# MotorControl.net
KiCad netlist of a schematic drawn in Altium Designer
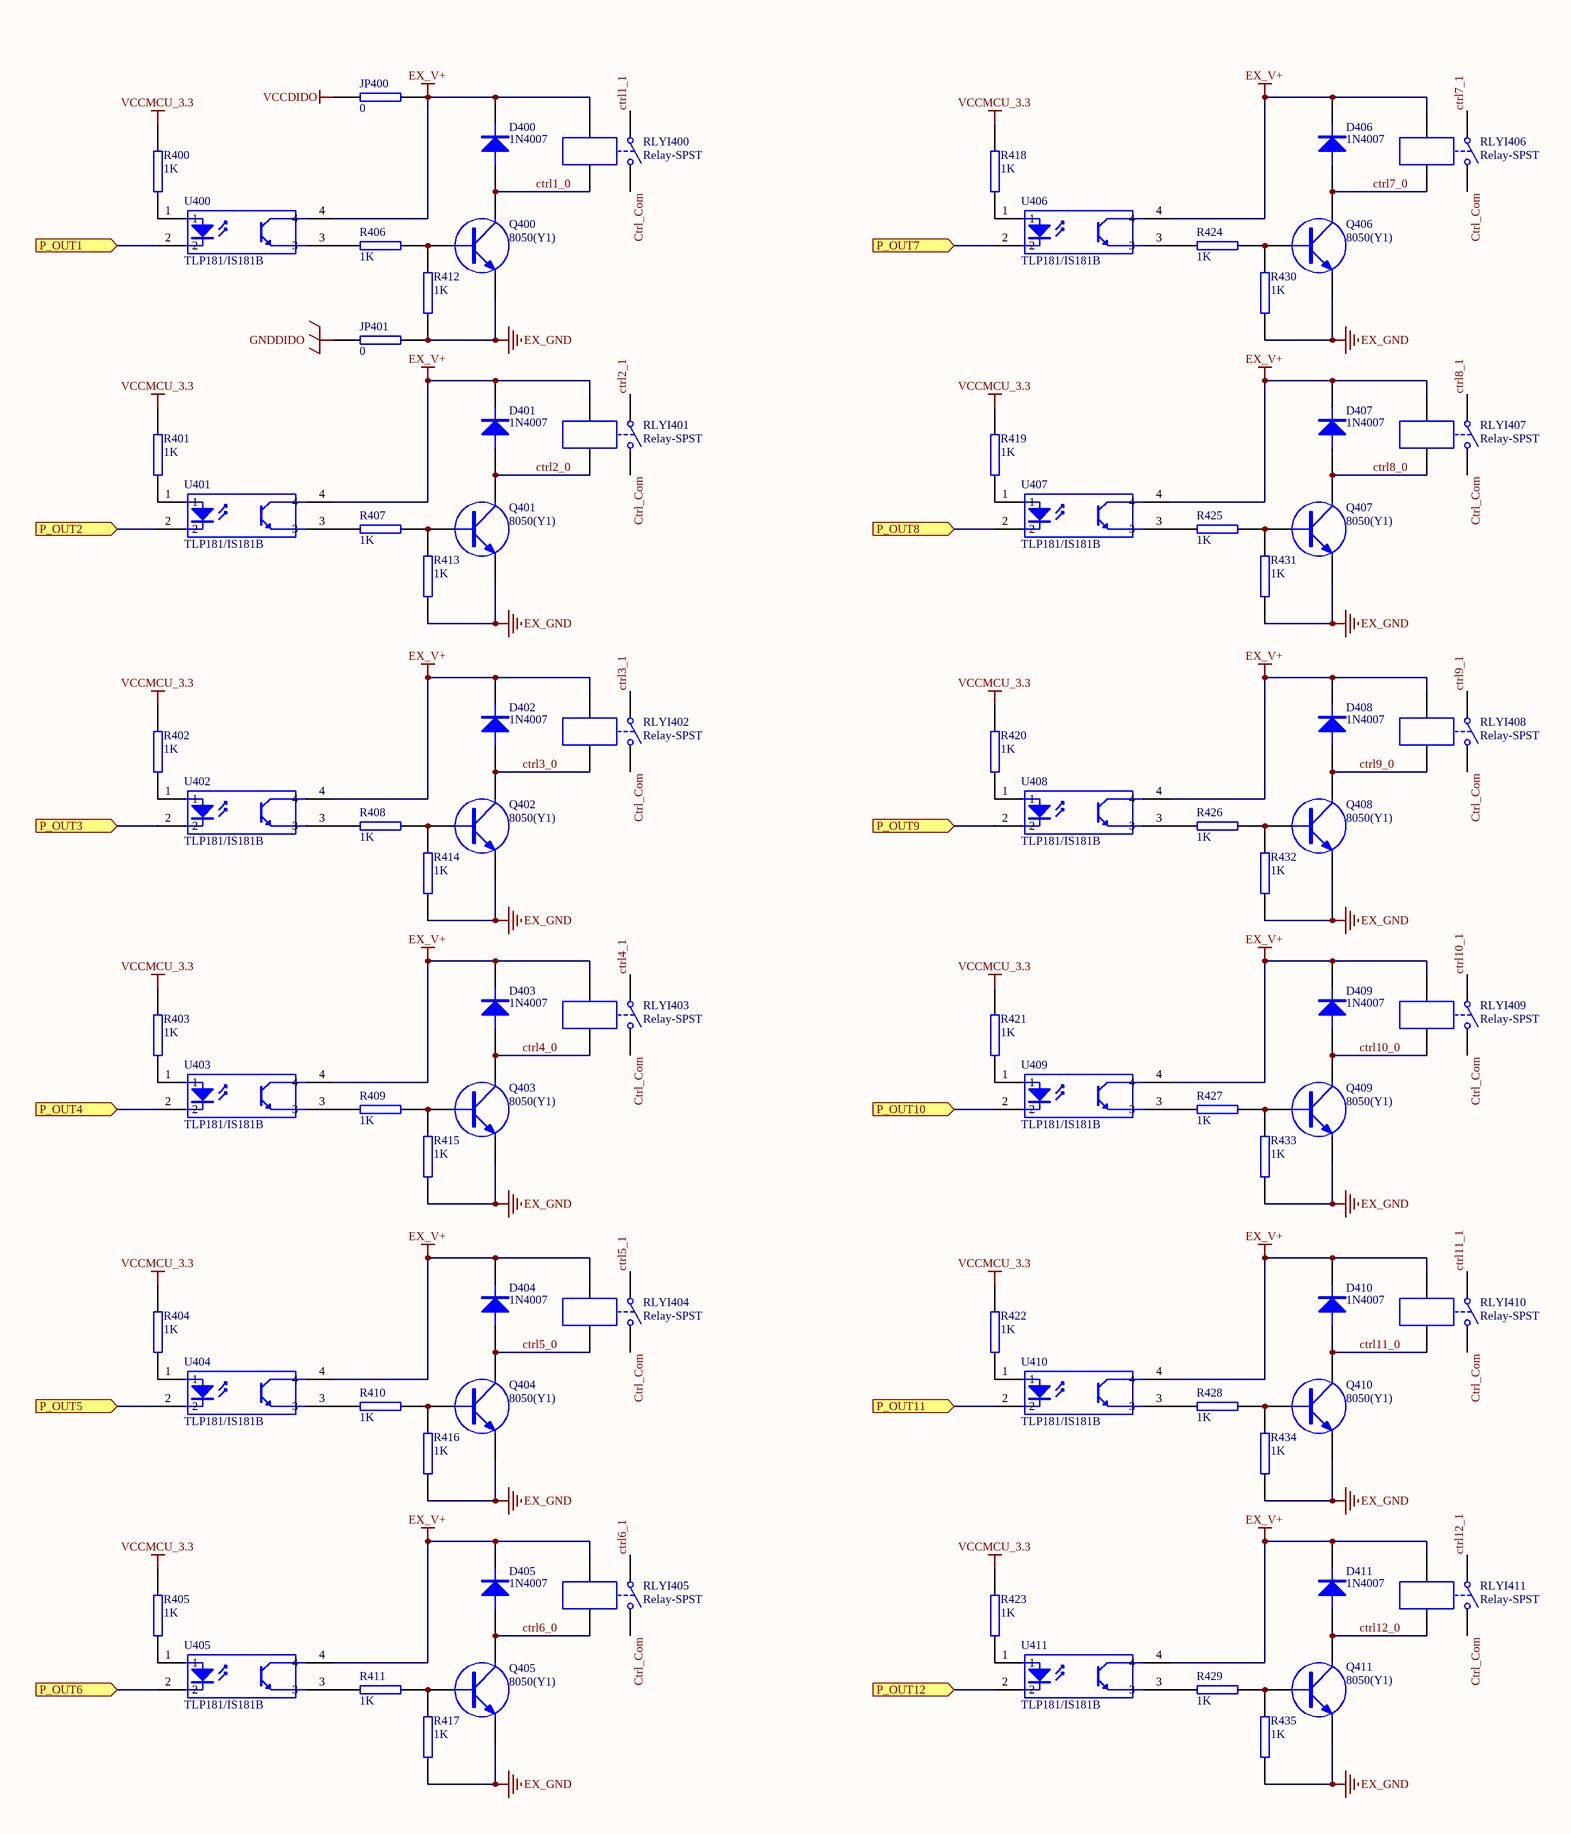
[diagram p0: MotorControl.SchDoc, left]
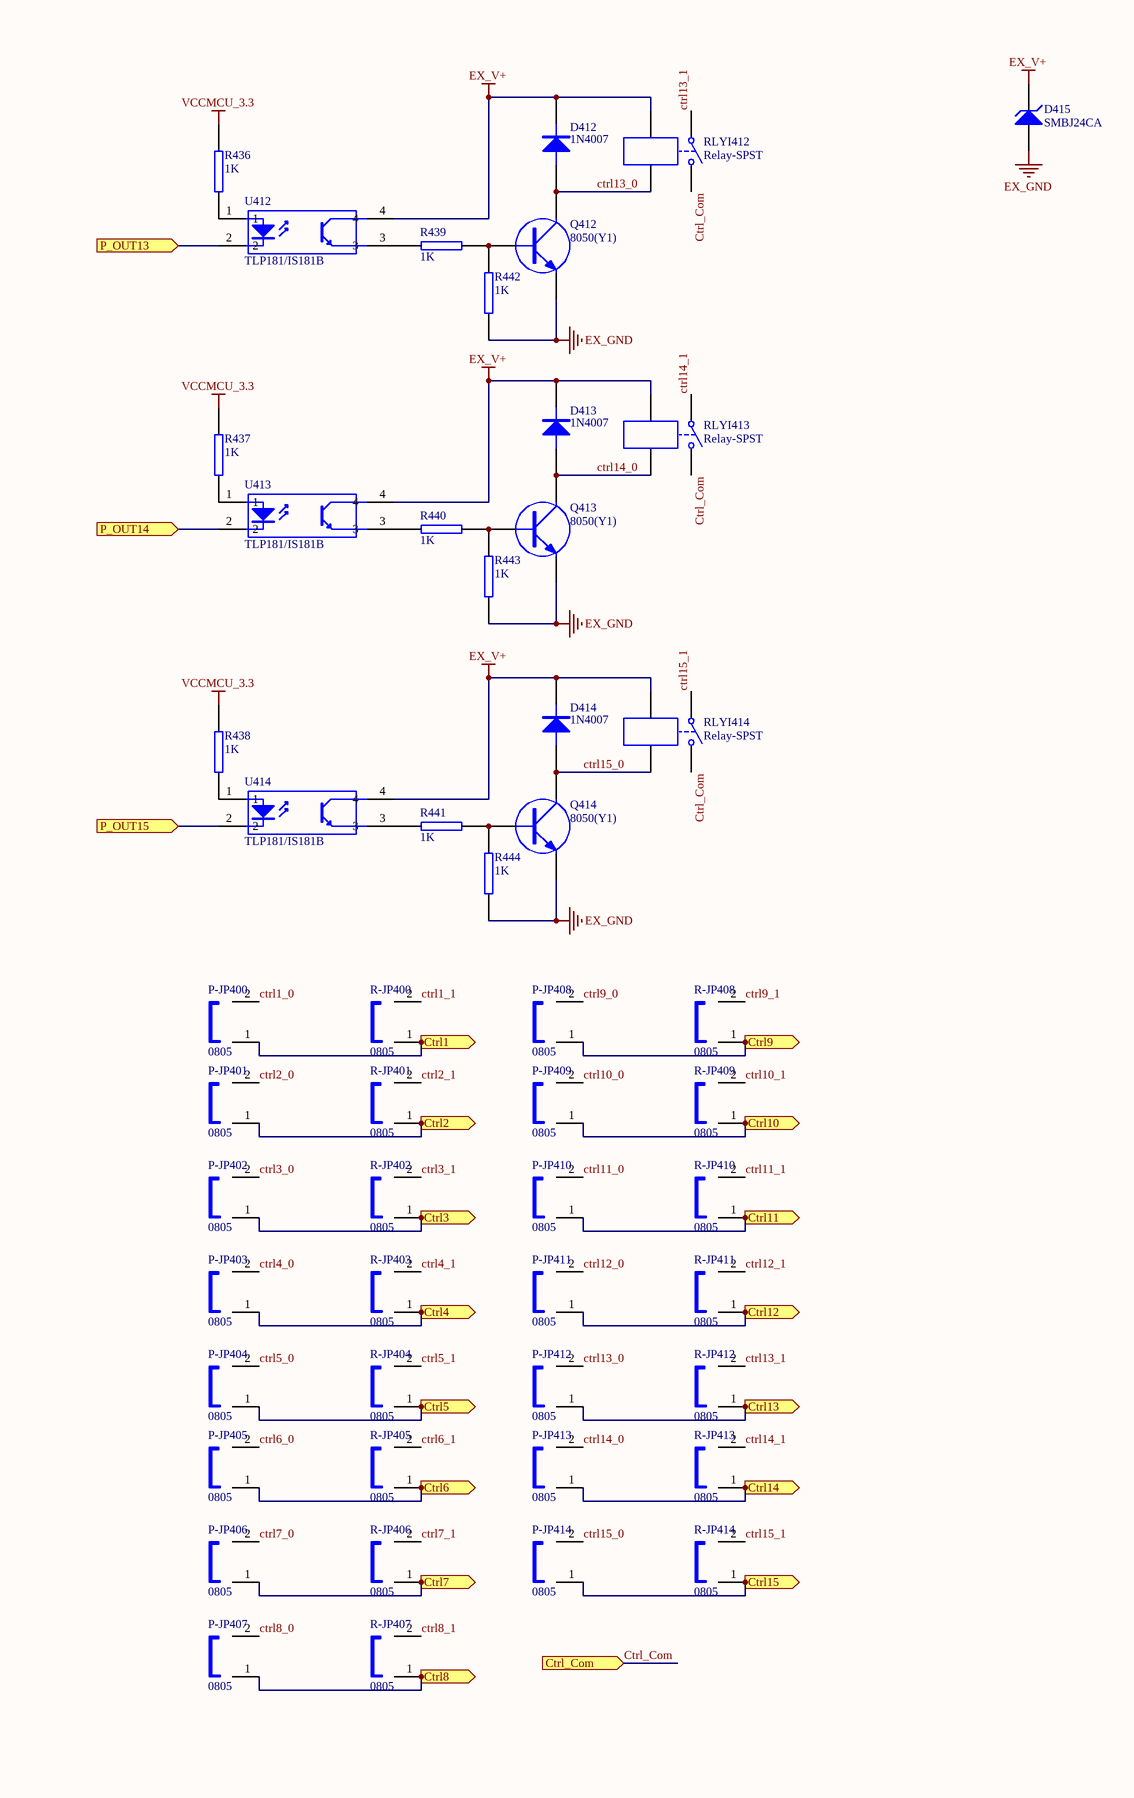
[diagram p1: MotorControl.SchDoc, right]

(export (version "E")
  (design (tool "Eeschema 10.0.6"))
  (components
    (comp (ref "D400")
      (value "1N4007")
      (footprint "SMA")
      (description "Diode")
      (libsource (lib "*") (part "DIODE"))
    )
    (comp (ref "D401")
      (value "1N4007")
      (footprint "SMA")
      (description "Diode")
      (libsource (lib "*") (part "DIODE"))
    )
    (comp (ref "D402")
      (value "1N4007")
      (footprint "SMA")
      (description "Diode")
      (libsource (lib "*") (part "DIODE"))
    )
    (comp (ref "D403")
      (value "1N4007")
      (footprint "SMA")
      (description "Diode")
      (libsource (lib "*") (part "DIODE"))
    )
    (comp (ref "D404")
      (value "1N4007")
      (footprint "SMA")
      (description "Diode")
      (libsource (lib "*") (part "DIODE"))
    )
    (comp (ref "D405")
      (value "1N4007")
      (footprint "SMA")
      (description "Diode")
      (libsource (lib "*") (part "DIODE"))
    )
    (comp (ref "D406")
      (value "1N4007")
      (footprint "SMA")
      (description "Diode")
      (libsource (lib "*") (part "DIODE"))
    )
    (comp (ref "D407")
      (value "1N4007")
      (footprint "SMA")
      (description "Diode")
      (libsource (lib "*") (part "DIODE"))
    )
    (comp (ref "D408")
      (value "1N4007")
      (footprint "SMA")
      (description "Diode")
      (libsource (lib "*") (part "DIODE"))
    )
    (comp (ref "D409")
      (value "1N4007")
      (footprint "SMA")
      (description "Diode")
      (libsource (lib "*") (part "DIODE"))
    )
    (comp (ref "D410")
      (value "1N4007")
      (footprint "SMA")
      (description "Diode")
      (libsource (lib "*") (part "DIODE"))
    )
    (comp (ref "D411")
      (value "1N4007")
      (footprint "SMA")
      (description "Diode")
      (libsource (lib "*") (part "DIODE"))
    )
    (comp (ref "D412")
      (value "1N4007")
      (footprint "SMA")
      (description "Diode")
      (libsource (lib "*") (part "DIODE"))
    )
    (comp (ref "D413")
      (value "1N4007")
      (footprint "SMA")
      (description "Diode")
      (libsource (lib "*") (part "DIODE"))
    )
    (comp (ref "D414")
      (value "1N4007")
      (footprint "SMA")
      (description "Diode")
      (libsource (lib "*") (part "DIODE"))
    )
    (comp (ref "D415")
      (value "SMBJ24CA")
      (footprint "SMB")
      (description "Zener Diode")
      (fields (field (name "PUBLISHER") "Altium Limited"))
      (libsource (lib "YGInfoSCHLib") (part "D Zener"))
    )
    (comp (ref "JP400") (value "0") (footprint "RESC_E0805_2012X50N") (libsource (lib "*") (part "RES2")))
    (comp (ref "JP401") (value "0") (footprint "RESC_E0805_2012X50N") (libsource (lib "*") (part "RES2")))
    (comp (ref "P-JP400")
      (value "0805")
      (footprint "RESC_E0805_2012X50N")
      (description "Jumper")
      (libsource (lib "YGInfoSCHLib") (part "JUMPER"))
    )
    (comp (ref "P-JP401")
      (value "0805")
      (footprint "RESC_E0805_2012X50N")
      (description "Jumper")
      (libsource (lib "YGInfoSCHLib") (part "JUMPER"))
    )
    (comp (ref "P-JP402")
      (value "0805")
      (footprint "RESC_E0805_2012X50N")
      (description "Jumper")
      (libsource (lib "YGInfoSCHLib") (part "JUMPER"))
    )
    (comp (ref "P-JP403")
      (value "0805")
      (footprint "RESC_E0805_2012X50N")
      (description "Jumper")
      (libsource (lib "YGInfoSCHLib") (part "JUMPER"))
    )
    (comp (ref "P-JP404")
      (value "0805")
      (footprint "RESC_E0805_2012X50N")
      (description "Jumper")
      (libsource (lib "YGInfoSCHLib") (part "JUMPER"))
    )
    (comp (ref "P-JP405")
      (value "0805")
      (footprint "RESC_E0805_2012X50N")
      (description "Jumper")
      (libsource (lib "YGInfoSCHLib") (part "JUMPER"))
    )
    (comp (ref "P-JP406")
      (value "0805")
      (footprint "RESC_E0805_2012X50N")
      (description "Jumper")
      (libsource (lib "YGInfoSCHLib") (part "JUMPER"))
    )
    (comp (ref "P-JP407")
      (value "0805")
      (footprint "RESC_E0805_2012X50N")
      (description "Jumper")
      (libsource (lib "YGInfoSCHLib") (part "JUMPER"))
    )
    (comp (ref "P-JP408")
      (value "0805")
      (footprint "RESC_E0805_2012X50N")
      (description "Jumper")
      (libsource (lib "YGInfoSCHLib") (part "JUMPER"))
    )
    (comp (ref "P-JP409")
      (value "0805")
      (footprint "RESC_E0805_2012X50N")
      (description "Jumper")
      (libsource (lib "YGInfoSCHLib") (part "JUMPER"))
    )
    (comp (ref "P-JP410")
      (value "0805")
      (footprint "RESC_E0805_2012X50N")
      (description "Jumper")
      (libsource (lib "YGInfoSCHLib") (part "JUMPER"))
    )
    (comp (ref "P-JP411")
      (value "0805")
      (footprint "RESC_E0805_2012X50N")
      (description "Jumper")
      (libsource (lib "YGInfoSCHLib") (part "JUMPER"))
    )
    (comp (ref "P-JP412")
      (value "0805")
      (footprint "RESC_E0805_2012X50N")
      (description "Jumper")
      (libsource (lib "YGInfoSCHLib") (part "JUMPER"))
    )
    (comp (ref "P-JP413")
      (value "0805")
      (footprint "RESC_E0805_2012X50N")
      (description "Jumper")
      (libsource (lib "YGInfoSCHLib") (part "JUMPER"))
    )
    (comp (ref "P-JP414")
      (value "0805")
      (footprint "RESC_E0805_2012X50N")
      (description "Jumper")
      (libsource (lib "YGInfoSCHLib") (part "JUMPER"))
    )
    (comp (ref "Q400")
      (value "8050(Y1)")
      (footprint "SOT23_95P280X110-3N")
      (libsource (lib "*") (part "BSS64"))
    )
    (comp (ref "Q401")
      (value "8050(Y1)")
      (footprint "SOT23_95P280X110-3N")
      (libsource (lib "*") (part "BSS64"))
    )
    (comp (ref "Q402")
      (value "8050(Y1)")
      (footprint "SOT23_95P280X110-3N")
      (libsource (lib "*") (part "BSS64"))
    )
    (comp (ref "Q403")
      (value "8050(Y1)")
      (footprint "SOT23_95P280X110-3N")
      (libsource (lib "*") (part "BSS64"))
    )
    (comp (ref "Q404")
      (value "8050(Y1)")
      (footprint "SOT23_95P280X110-3N")
      (libsource (lib "*") (part "BSS64"))
    )
    (comp (ref "Q405")
      (value "8050(Y1)")
      (footprint "SOT23_95P280X110-3N")
      (libsource (lib "*") (part "BSS64"))
    )
    (comp (ref "Q406")
      (value "8050(Y1)")
      (footprint "SOT23_95P280X110-3N")
      (libsource (lib "*") (part "BSS64"))
    )
    (comp (ref "Q407")
      (value "8050(Y1)")
      (footprint "SOT23_95P280X110-3N")
      (libsource (lib "*") (part "BSS64"))
    )
    (comp (ref "Q408")
      (value "8050(Y1)")
      (footprint "SOT23_95P280X110-3N")
      (libsource (lib "*") (part "BSS64"))
    )
    (comp (ref "Q409")
      (value "8050(Y1)")
      (footprint "SOT23_95P280X110-3N")
      (libsource (lib "*") (part "BSS64"))
    )
    (comp (ref "Q410")
      (value "8050(Y1)")
      (footprint "SOT23_95P280X110-3N")
      (libsource (lib "*") (part "BSS64"))
    )
    (comp (ref "Q411")
      (value "8050(Y1)")
      (footprint "SOT23_95P280X110-3N")
      (libsource (lib "*") (part "BSS64"))
    )
    (comp (ref "Q412")
      (value "8050(Y1)")
      (footprint "SOT23_95P280X110-3N")
      (libsource (lib "*") (part "BSS64"))
    )
    (comp (ref "Q413")
      (value "8050(Y1)")
      (footprint "SOT23_95P280X110-3N")
      (libsource (lib "*") (part "BSS64"))
    )
    (comp (ref "Q414")
      (value "8050(Y1)")
      (footprint "SOT23_95P280X110-3N")
      (libsource (lib "*") (part "BSS64"))
    )
    (comp (ref "R-JP400")
      (value "0805")
      (footprint "RESC_E0805_2012X50N")
      (description "Jumper")
      (libsource (lib "YGInfoSCHLib") (part "JUMPER"))
    )
    (comp (ref "R-JP401")
      (value "0805")
      (footprint "RESC_E0805_2012X50N")
      (description "Jumper")
      (libsource (lib "YGInfoSCHLib") (part "JUMPER"))
    )
    (comp (ref "R-JP402")
      (value "0805")
      (footprint "RESC_E0805_2012X50N")
      (description "Jumper")
      (libsource (lib "YGInfoSCHLib") (part "JUMPER"))
    )
    (comp (ref "R-JP403")
      (value "0805")
      (footprint "RESC_E0805_2012X50N")
      (description "Jumper")
      (libsource (lib "YGInfoSCHLib") (part "JUMPER"))
    )
    (comp (ref "R-JP404")
      (value "0805")
      (footprint "RESC_E0805_2012X50N")
      (description "Jumper")
      (libsource (lib "YGInfoSCHLib") (part "JUMPER"))
    )
    (comp (ref "R-JP405")
      (value "0805")
      (footprint "RESC_E0805_2012X50N")
      (description "Jumper")
      (libsource (lib "YGInfoSCHLib") (part "JUMPER"))
    )
    (comp (ref "R-JP406")
      (value "0805")
      (footprint "RESC_E0805_2012X50N")
      (description "Jumper")
      (libsource (lib "YGInfoSCHLib") (part "JUMPER"))
    )
    (comp (ref "R-JP407")
      (value "0805")
      (footprint "RESC_E0805_2012X50N")
      (description "Jumper")
      (libsource (lib "YGInfoSCHLib") (part "JUMPER"))
    )
    (comp (ref "R-JP408")
      (value "0805")
      (footprint "RESC_E0805_2012X50N")
      (description "Jumper")
      (libsource (lib "YGInfoSCHLib") (part "JUMPER"))
    )
    (comp (ref "R-JP409")
      (value "0805")
      (footprint "RESC_E0805_2012X50N")
      (description "Jumper")
      (libsource (lib "YGInfoSCHLib") (part "JUMPER"))
    )
    (comp (ref "R-JP410")
      (value "0805")
      (footprint "RESC_E0805_2012X50N")
      (description "Jumper")
      (libsource (lib "YGInfoSCHLib") (part "JUMPER"))
    )
    (comp (ref "R-JP411")
      (value "0805")
      (footprint "RESC_E0805_2012X50N")
      (description "Jumper")
      (libsource (lib "YGInfoSCHLib") (part "JUMPER"))
    )
    (comp (ref "R-JP412")
      (value "0805")
      (footprint "RESC_E0805_2012X50N")
      (description "Jumper")
      (libsource (lib "YGInfoSCHLib") (part "JUMPER"))
    )
    (comp (ref "R-JP413")
      (value "0805")
      (footprint "RESC_E0805_2012X50N")
      (description "Jumper")
      (libsource (lib "YGInfoSCHLib") (part "JUMPER"))
    )
    (comp (ref "R-JP414")
      (value "0805")
      (footprint "RESC_E0805_2012X50N")
      (description "Jumper")
      (libsource (lib "YGInfoSCHLib") (part "JUMPER"))
    )
    (comp (ref "R400") (value "1K") (footprint "RESC_E0805_2012X50N") (libsource (lib "*") (part "RES2")))
    (comp (ref "R401") (value "1K") (footprint "RESC_E0805_2012X50N") (libsource (lib "*") (part "RES2")))
    (comp (ref "R402") (value "1K") (footprint "RESC_E0805_2012X50N") (libsource (lib "*") (part "RES2")))
    (comp (ref "R403") (value "1K") (footprint "RESC_E0805_2012X50N") (libsource (lib "*") (part "RES2")))
    (comp (ref "R404") (value "1K") (footprint "RESC_E0805_2012X50N") (libsource (lib "*") (part "RES2")))
    (comp (ref "R405") (value "1K") (footprint "RESC_E0805_2012X50N") (libsource (lib "*") (part "RES2")))
    (comp (ref "R406") (value "1K") (footprint "RESC_E0805_2012X50N") (libsource (lib "*") (part "RES2")))
    (comp (ref "R407") (value "1K") (footprint "RESC_E0805_2012X50N") (libsource (lib "*") (part "RES2")))
    (comp (ref "R408") (value "1K") (footprint "RESC_E0805_2012X50N") (libsource (lib "*") (part "RES2")))
    (comp (ref "R409") (value "1K") (footprint "RESC_E0805_2012X50N") (libsource (lib "*") (part "RES2")))
    (comp (ref "R410") (value "1K") (footprint "RESC_E0805_2012X50N") (libsource (lib "*") (part "RES2")))
    (comp (ref "R411") (value "1K") (footprint "RESC_E0805_2012X50N") (libsource (lib "*") (part "RES2")))
    (comp (ref "R412") (value "1K") (footprint "RESC_E0805_2012X50N") (libsource (lib "*") (part "RES2")))
    (comp (ref "R413") (value "1K") (footprint "RESC_E0805_2012X50N") (libsource (lib "*") (part "RES2")))
    (comp (ref "R414") (value "1K") (footprint "RESC_E0805_2012X50N") (libsource (lib "*") (part "RES2")))
    (comp (ref "R415") (value "1K") (footprint "RESC_E0805_2012X50N") (libsource (lib "*") (part "RES2")))
    (comp (ref "R416") (value "1K") (footprint "RESC_E0805_2012X50N") (libsource (lib "*") (part "RES2")))
    (comp (ref "R417") (value "1K") (footprint "RESC_E0805_2012X50N") (libsource (lib "*") (part "RES2")))
    (comp (ref "R418") (value "1K") (footprint "RESC_E0805_2012X50N") (libsource (lib "*") (part "RES2")))
    (comp (ref "R419") (value "1K") (footprint "RESC_E0805_2012X50N") (libsource (lib "*") (part "RES2")))
    (comp (ref "R420") (value "1K") (footprint "RESC_E0805_2012X50N") (libsource (lib "*") (part "RES2")))
    (comp (ref "R421") (value "1K") (footprint "RESC_E0805_2012X50N") (libsource (lib "*") (part "RES2")))
    (comp (ref "R422") (value "1K") (footprint "RESC_E0805_2012X50N") (libsource (lib "*") (part "RES2")))
    (comp (ref "R423") (value "1K") (footprint "RESC_E0805_2012X50N") (libsource (lib "*") (part "RES2")))
    (comp (ref "R424") (value "1K") (footprint "RESC_E0805_2012X50N") (libsource (lib "*") (part "RES2")))
    (comp (ref "R425") (value "1K") (footprint "RESC_E0805_2012X50N") (libsource (lib "*") (part "RES2")))
    (comp (ref "R426") (value "1K") (footprint "RESC_E0805_2012X50N") (libsource (lib "*") (part "RES2")))
    (comp (ref "R427") (value "1K") (footprint "RESC_E0805_2012X50N") (libsource (lib "*") (part "RES2")))
    (comp (ref "R428") (value "1K") (footprint "RESC_E0805_2012X50N") (libsource (lib "*") (part "RES2")))
    (comp (ref "R429") (value "1K") (footprint "RESC_E0805_2012X50N") (libsource (lib "*") (part "RES2")))
    (comp (ref "R430") (value "1K") (footprint "RESC_E0805_2012X50N") (libsource (lib "*") (part "RES2")))
    (comp (ref "R431") (value "1K") (footprint "RESC_E0805_2012X50N") (libsource (lib "*") (part "RES2")))
    (comp (ref "R432") (value "1K") (footprint "RESC_E0805_2012X50N") (libsource (lib "*") (part "RES2")))
    (comp (ref "R433") (value "1K") (footprint "RESC_E0805_2012X50N") (libsource (lib "*") (part "RES2")))
    (comp (ref "R434") (value "1K") (footprint "RESC_E0805_2012X50N") (libsource (lib "*") (part "RES2")))
    (comp (ref "R435") (value "1K") (footprint "RESC_E0805_2012X50N") (libsource (lib "*") (part "RES2")))
    (comp (ref "R436") (value "1K") (footprint "RESC_E0805_2012X50N") (libsource (lib "*") (part "RES2")))
    (comp (ref "R437") (value "1K") (footprint "RESC_E0805_2012X50N") (libsource (lib "*") (part "RES2")))
    (comp (ref "R438") (value "1K") (footprint "RESC_E0805_2012X50N") (libsource (lib "*") (part "RES2")))
    (comp (ref "R439") (value "1K") (footprint "RESC_E0805_2012X50N") (libsource (lib "*") (part "RES2")))
    (comp (ref "R440") (value "1K") (footprint "RESC_E0805_2012X50N") (libsource (lib "*") (part "RES2")))
    (comp (ref "R441") (value "1K") (footprint "RESC_E0805_2012X50N") (libsource (lib "*") (part "RES2")))
    (comp (ref "R442") (value "1K") (footprint "RESC_E0805_2012X50N") (libsource (lib "*") (part "RES2")))
    (comp (ref "R443") (value "1K") (footprint "RESC_E0805_2012X50N") (libsource (lib "*") (part "RES2")))
    (comp (ref "R444") (value "1K") (footprint "RESC_E0805_2012X50N") (libsource (lib "*") (part "RES2")))
    (comp (ref "RLYI400")
      (value "Relay-SPST")
      (footprint "JDQ24V")
      (description "Single-Pole Single-Throw Relay")
      (fields (field (name "PUBLISHER") "Altium Limited"))
      (libsource (lib "Miscellaneous Devices") (part "Relay-SPST"))
    )
    (comp (ref "RLYI401")
      (value "Relay-SPST")
      (footprint "JDQ24V")
      (description "Single-Pole Single-Throw Relay")
      (fields (field (name "PUBLISHER") "Altium Limited"))
      (libsource (lib "Miscellaneous Devices") (part "Relay-SPST"))
    )
    (comp (ref "RLYI402")
      (value "Relay-SPST")
      (footprint "JDQ24V")
      (description "Single-Pole Single-Throw Relay")
      (fields (field (name "PUBLISHER") "Altium Limited"))
      (libsource (lib "Miscellaneous Devices") (part "Relay-SPST"))
    )
    (comp (ref "RLYI403")
      (value "Relay-SPST")
      (footprint "JDQ24V")
      (description "Single-Pole Single-Throw Relay")
      (fields (field (name "PUBLISHER") "Altium Limited"))
      (libsource (lib "Miscellaneous Devices") (part "Relay-SPST"))
    )
    (comp (ref "RLYI404")
      (value "Relay-SPST")
      (footprint "JDQ24V")
      (description "Single-Pole Single-Throw Relay")
      (fields (field (name "PUBLISHER") "Altium Limited"))
      (libsource (lib "Miscellaneous Devices") (part "Relay-SPST"))
    )
    (comp (ref "RLYI405")
      (value "Relay-SPST")
      (footprint "JDQ24V")
      (description "Single-Pole Single-Throw Relay")
      (fields (field (name "PUBLISHER") "Altium Limited"))
      (libsource (lib "Miscellaneous Devices") (part "Relay-SPST"))
    )
    (comp (ref "RLYI406")
      (value "Relay-SPST")
      (footprint "JDQ24V")
      (description "Single-Pole Single-Throw Relay")
      (fields (field (name "PUBLISHER") "Altium Limited"))
      (libsource (lib "Miscellaneous Devices") (part "Relay-SPST"))
    )
    (comp (ref "RLYI407")
      (value "Relay-SPST")
      (footprint "JDQ24V")
      (description "Single-Pole Single-Throw Relay")
      (fields (field (name "PUBLISHER") "Altium Limited"))
      (libsource (lib "Miscellaneous Devices") (part "Relay-SPST"))
    )
    (comp (ref "RLYI408")
      (value "Relay-SPST")
      (footprint "JDQ24V")
      (description "Single-Pole Single-Throw Relay")
      (fields (field (name "PUBLISHER") "Altium Limited"))
      (libsource (lib "Miscellaneous Devices") (part "Relay-SPST"))
    )
    (comp (ref "RLYI409")
      (value "Relay-SPST")
      (footprint "JDQ24V")
      (description "Single-Pole Single-Throw Relay")
      (fields (field (name "PUBLISHER") "Altium Limited"))
      (libsource (lib "Miscellaneous Devices") (part "Relay-SPST"))
    )
    (comp (ref "RLYI410")
      (value "Relay-SPST")
      (footprint "JDQ24V")
      (description "Single-Pole Single-Throw Relay")
      (fields (field (name "PUBLISHER") "Altium Limited"))
      (libsource (lib "Miscellaneous Devices") (part "Relay-SPST"))
    )
    (comp (ref "RLYI411")
      (value "Relay-SPST")
      (footprint "JDQ24V")
      (description "Single-Pole Single-Throw Relay")
      (fields (field (name "PUBLISHER") "Altium Limited"))
      (libsource (lib "Miscellaneous Devices") (part "Relay-SPST"))
    )
    (comp (ref "RLYI412")
      (value "Relay-SPST")
      (footprint "JDQ24V")
      (description "Single-Pole Single-Throw Relay")
      (fields (field (name "PUBLISHER") "Altium Limited"))
      (libsource (lib "Miscellaneous Devices") (part "Relay-SPST"))
    )
    (comp (ref "RLYI413")
      (value "Relay-SPST")
      (footprint "JDQ24V")
      (description "Single-Pole Single-Throw Relay")
      (fields (field (name "PUBLISHER") "Altium Limited"))
      (libsource (lib "Miscellaneous Devices") (part "Relay-SPST"))
    )
    (comp (ref "RLYI414")
      (value "Relay-SPST")
      (footprint "JDQ24V")
      (description "Single-Pole Single-Throw Relay")
      (fields (field (name "PUBLISHER") "Altium Limited"))
      (libsource (lib "Miscellaneous Devices") (part "Relay-SPST"))
    )
    (comp (ref "U400")
      (value "TLP181/IS181B")
      (footprint "TLP181")
      (description "光耦隔离")
      (libsource (lib "YGInfoSCHLib") (part "TLP181"))
    )
    (comp (ref "U401")
      (value "TLP181/IS181B")
      (footprint "TLP181")
      (description "光耦隔离")
      (libsource (lib "YGInfoSCHLib") (part "TLP181"))
    )
    (comp (ref "U402")
      (value "TLP181/IS181B")
      (footprint "TLP181")
      (description "光耦隔离")
      (libsource (lib "YGInfoSCHLib") (part "TLP181"))
    )
    (comp (ref "U403")
      (value "TLP181/IS181B")
      (footprint "TLP181")
      (description "光耦隔离")
      (libsource (lib "YGInfoSCHLib") (part "TLP181"))
    )
    (comp (ref "U404")
      (value "TLP181/IS181B")
      (footprint "TLP181")
      (description "光耦隔离")
      (libsource (lib "YGInfoSCHLib") (part "TLP181"))
    )
    (comp (ref "U405")
      (value "TLP181/IS181B")
      (footprint "TLP181")
      (description "光耦隔离")
      (libsource (lib "YGInfoSCHLib") (part "TLP181"))
    )
    (comp (ref "U406")
      (value "TLP181/IS181B")
      (footprint "TLP181")
      (description "光耦隔离")
      (libsource (lib "YGInfoSCHLib") (part "TLP181"))
    )
    (comp (ref "U407")
      (value "TLP181/IS181B")
      (footprint "TLP181")
      (description "光耦隔离")
      (libsource (lib "YGInfoSCHLib") (part "TLP181"))
    )
    (comp (ref "U408")
      (value "TLP181/IS181B")
      (footprint "TLP181")
      (description "光耦隔离")
      (libsource (lib "YGInfoSCHLib") (part "TLP181"))
    )
    (comp (ref "U409")
      (value "TLP181/IS181B")
      (footprint "TLP181")
      (description "光耦隔离")
      (libsource (lib "YGInfoSCHLib") (part "TLP181"))
    )
    (comp (ref "U410")
      (value "TLP181/IS181B")
      (footprint "TLP181")
      (description "光耦隔离")
      (libsource (lib "YGInfoSCHLib") (part "TLP181"))
    )
    (comp (ref "U411")
      (value "TLP181/IS181B")
      (footprint "TLP181")
      (description "光耦隔离")
      (libsource (lib "YGInfoSCHLib") (part "TLP181"))
    )
    (comp (ref "U412")
      (value "TLP181/IS181B")
      (footprint "TLP181")
      (description "光耦隔离")
      (libsource (lib "YGInfoSCHLib") (part "TLP181"))
    )
    (comp (ref "U413")
      (value "TLP181/IS181B")
      (footprint "TLP181")
      (description "光耦隔离")
      (libsource (lib "YGInfoSCHLib") (part "TLP181"))
    )
    (comp (ref "U414")
      (value "TLP181/IS181B")
      (footprint "TLP181")
      (description "光耦隔离")
      (libsource (lib "YGInfoSCHLib") (part "TLP181"))
    )
  )
  (nets
    (net (code "1") (name "/Ctrl1") (class "Default")
      (node (ref "P-JP400") (pin "1") (pinfunction "1_1") (pintype "passive"))
      (node (ref "R-JP400") (pin "1") (pinfunction "1_1") (pintype "passive"))
    )
    (net (code "2") (name "/Ctrl2") (class "Default")
      (node (ref "P-JP401") (pin "1") (pinfunction "1_1") (pintype "passive"))
      (node (ref "R-JP401") (pin "1") (pinfunction "1_1") (pintype "passive"))
    )
    (net (code "3") (name "/Ctrl3") (class "Default")
      (node (ref "P-JP402") (pin "1") (pinfunction "1_1") (pintype "passive"))
      (node (ref "R-JP402") (pin "1") (pinfunction "1_1") (pintype "passive"))
    )
    (net (code "4") (name "/Ctrl4") (class "Default")
      (node (ref "P-JP403") (pin "1") (pinfunction "1_1") (pintype "passive"))
      (node (ref "R-JP403") (pin "1") (pinfunction "1_1") (pintype "passive"))
    )
    (net (code "5") (name "/Ctrl5") (class "Default")
      (node (ref "P-JP404") (pin "1") (pinfunction "1_1") (pintype "passive"))
      (node (ref "R-JP404") (pin "1") (pinfunction "1_1") (pintype "passive"))
    )
    (net (code "6") (name "/Ctrl6") (class "Default")
      (node (ref "P-JP405") (pin "1") (pinfunction "1_1") (pintype "passive"))
      (node (ref "R-JP405") (pin "1") (pinfunction "1_1") (pintype "passive"))
    )
    (net (code "7") (name "/Ctrl7") (class "Default")
      (node (ref "P-JP406") (pin "1") (pinfunction "1_1") (pintype "passive"))
      (node (ref "R-JP406") (pin "1") (pinfunction "1_1") (pintype "passive"))
    )
    (net (code "8") (name "/Ctrl8") (class "Default")
      (node (ref "P-JP407") (pin "1") (pinfunction "1_1") (pintype "passive"))
      (node (ref "R-JP407") (pin "1") (pinfunction "1_1") (pintype "passive"))
    )
    (net (code "9") (name "/Ctrl9") (class "Default")
      (node (ref "P-JP408") (pin "1") (pinfunction "1_1") (pintype "passive"))
      (node (ref "R-JP408") (pin "1") (pinfunction "1_1") (pintype "passive"))
    )
    (net (code "10") (name "/Ctrl10") (class "Default")
      (node (ref "P-JP409") (pin "1") (pinfunction "1_1") (pintype "passive"))
      (node (ref "R-JP409") (pin "1") (pinfunction "1_1") (pintype "passive"))
    )
    (net (code "11") (name "/Ctrl11") (class "Default")
      (node (ref "P-JP410") (pin "1") (pinfunction "1_1") (pintype "passive"))
      (node (ref "R-JP410") (pin "1") (pinfunction "1_1") (pintype "passive"))
    )
    (net (code "12") (name "/Ctrl12") (class "Default")
      (node (ref "P-JP411") (pin "1") (pinfunction "1_1") (pintype "passive"))
      (node (ref "R-JP411") (pin "1") (pinfunction "1_1") (pintype "passive"))
    )
    (net (code "13") (name "/Ctrl13") (class "Default")
      (node (ref "P-JP412") (pin "1") (pinfunction "1_1") (pintype "passive"))
      (node (ref "R-JP412") (pin "1") (pinfunction "1_1") (pintype "passive"))
    )
    (net (code "14") (name "/Ctrl14") (class "Default")
      (node (ref "P-JP413") (pin "1") (pinfunction "1_1") (pintype "passive"))
      (node (ref "R-JP413") (pin "1") (pinfunction "1_1") (pintype "passive"))
    )
    (net (code "15") (name "/Ctrl15") (class "Default")
      (node (ref "P-JP414") (pin "1") (pinfunction "1_1") (pintype "passive"))
      (node (ref "R-JP414") (pin "1") (pinfunction "1_1") (pintype "passive"))
    )
    (net (code "16") (name "/Ctrl_Com") (class "Default")
      (node (ref "RLYI400") (pin "2") (pinfunction "2_2") (pintype "passive"))
      (node (ref "RLYI401") (pin "2") (pinfunction "2_2") (pintype "passive"))
      (node (ref "RLYI402") (pin "2") (pinfunction "2_2") (pintype "passive"))
      (node (ref "RLYI403") (pin "2") (pinfunction "2_2") (pintype "passive"))
      (node (ref "RLYI404") (pin "2") (pinfunction "2_2") (pintype "passive"))
      (node (ref "RLYI405") (pin "2") (pinfunction "2_2") (pintype "passive"))
      (node (ref "RLYI406") (pin "2") (pinfunction "2_2") (pintype "passive"))
      (node (ref "RLYI407") (pin "2") (pinfunction "2_2") (pintype "passive"))
      (node (ref "RLYI408") (pin "2") (pinfunction "2_2") (pintype "passive"))
      (node (ref "RLYI409") (pin "2") (pinfunction "2_2") (pintype "passive"))
      (node (ref "RLYI410") (pin "2") (pinfunction "2_2") (pintype "passive"))
      (node (ref "RLYI411") (pin "2") (pinfunction "2_2") (pintype "passive"))
      (node (ref "RLYI412") (pin "2") (pinfunction "2_2") (pintype "passive"))
      (node (ref "RLYI413") (pin "2") (pinfunction "2_2") (pintype "passive"))
      (node (ref "RLYI414") (pin "2") (pinfunction "2_2") (pintype "passive"))
    )
    (net (code "17") (name "/P_OUT1") (class "Default")
      (node (ref "U400") (pin "2") (pinfunction "2_2") (pintype "passive"))
    )
    (net (code "18") (name "/P_OUT2") (class "Default")
      (node (ref "U401") (pin "2") (pinfunction "2_2") (pintype "passive"))
    )
    (net (code "19") (name "/P_OUT3") (class "Default")
      (node (ref "U402") (pin "2") (pinfunction "2_2") (pintype "passive"))
    )
    (net (code "20") (name "/P_OUT4") (class "Default")
      (node (ref "U403") (pin "2") (pinfunction "2_2") (pintype "passive"))
    )
    (net (code "21") (name "/P_OUT5") (class "Default")
      (node (ref "U404") (pin "2") (pinfunction "2_2") (pintype "passive"))
    )
    (net (code "22") (name "/P_OUT6") (class "Default")
      (node (ref "U405") (pin "2") (pinfunction "2_2") (pintype "passive"))
    )
    (net (code "23") (name "/P_OUT7") (class "Default")
      (node (ref "U406") (pin "2") (pinfunction "2_2") (pintype "passive"))
    )
    (net (code "24") (name "/P_OUT8") (class "Default")
      (node (ref "U407") (pin "2") (pinfunction "2_2") (pintype "passive"))
    )
    (net (code "25") (name "/P_OUT9") (class "Default")
      (node (ref "U408") (pin "2") (pinfunction "2_2") (pintype "passive"))
    )
    (net (code "26") (name "/P_OUT10") (class "Default")
      (node (ref "U409") (pin "2") (pinfunction "2_2") (pintype "passive"))
    )
    (net (code "27") (name "/P_OUT11") (class "Default")
      (node (ref "U410") (pin "2") (pinfunction "2_2") (pintype "passive"))
    )
    (net (code "28") (name "/P_OUT12") (class "Default")
      (node (ref "U411") (pin "2") (pinfunction "2_2") (pintype "passive"))
    )
    (net (code "29") (name "/P_OUT13") (class "Default")
      (node (ref "U412") (pin "2") (pinfunction "2_2") (pintype "passive"))
    )
    (net (code "30") (name "/P_OUT14") (class "Default")
      (node (ref "U413") (pin "2") (pinfunction "2_2") (pintype "passive"))
    )
    (net (code "31") (name "/P_OUT15") (class "Default")
      (node (ref "U414") (pin "2") (pinfunction "2_2") (pintype "passive"))
    )
    (net (code "32") (name "/ctrl1_0") (class "Default")
      (node (ref "D400") (pin "1") (pinfunction "A_1") (pintype "passive"))
      (node (ref "P-JP400") (pin "2") (pinfunction "2_2") (pintype "passive"))
      (node (ref "Q400") (pin "3") (pinfunction "C_3") (pintype "passive"))
      (node (ref "RLYI400") (pin "4") (pinfunction "4_4") (pintype "passive"))
    )
    (net (code "33") (name "/ctrl1_1") (class "Default")
      (node (ref "R-JP400") (pin "2") (pinfunction "2_2") (pintype "passive"))
      (node (ref "RLYI400") (pin "1") (pinfunction "1_1") (pintype "passive"))
    )
    (net (code "34") (name "/ctrl2_0") (class "Default")
      (node (ref "D401") (pin "1") (pinfunction "A_1") (pintype "passive"))
      (node (ref "P-JP401") (pin "2") (pinfunction "2_2") (pintype "passive"))
      (node (ref "Q401") (pin "3") (pinfunction "C_3") (pintype "passive"))
      (node (ref "RLYI401") (pin "4") (pinfunction "4_4") (pintype "passive"))
    )
    (net (code "35") (name "/ctrl2_1") (class "Default")
      (node (ref "R-JP401") (pin "2") (pinfunction "2_2") (pintype "passive"))
      (node (ref "RLYI401") (pin "1") (pinfunction "1_1") (pintype "passive"))
    )
    (net (code "36") (name "/ctrl3_0") (class "Default")
      (node (ref "D402") (pin "1") (pinfunction "A_1") (pintype "passive"))
      (node (ref "P-JP402") (pin "2") (pinfunction "2_2") (pintype "passive"))
      (node (ref "Q402") (pin "3") (pinfunction "C_3") (pintype "passive"))
      (node (ref "RLYI402") (pin "4") (pinfunction "4_4") (pintype "passive"))
    )
    (net (code "37") (name "/ctrl3_1") (class "Default")
      (node (ref "R-JP402") (pin "2") (pinfunction "2_2") (pintype "passive"))
      (node (ref "RLYI402") (pin "1") (pinfunction "1_1") (pintype "passive"))
    )
    (net (code "38") (name "/ctrl4_0") (class "Default")
      (node (ref "D403") (pin "1") (pinfunction "A_1") (pintype "passive"))
      (node (ref "P-JP403") (pin "2") (pinfunction "2_2") (pintype "passive"))
      (node (ref "Q403") (pin "3") (pinfunction "C_3") (pintype "passive"))
      (node (ref "RLYI403") (pin "4") (pinfunction "4_4") (pintype "passive"))
    )
    (net (code "39") (name "/ctrl4_1") (class "Default")
      (node (ref "R-JP403") (pin "2") (pinfunction "2_2") (pintype "passive"))
      (node (ref "RLYI403") (pin "1") (pinfunction "1_1") (pintype "passive"))
    )
    (net (code "40") (name "/ctrl5_0") (class "Default")
      (node (ref "D404") (pin "1") (pinfunction "A_1") (pintype "passive"))
      (node (ref "P-JP404") (pin "2") (pinfunction "2_2") (pintype "passive"))
      (node (ref "Q404") (pin "3") (pinfunction "C_3") (pintype "passive"))
      (node (ref "RLYI404") (pin "4") (pinfunction "4_4") (pintype "passive"))
    )
    (net (code "41") (name "/ctrl5_1") (class "Default")
      (node (ref "R-JP404") (pin "2") (pinfunction "2_2") (pintype "passive"))
      (node (ref "RLYI404") (pin "1") (pinfunction "1_1") (pintype "passive"))
    )
    (net (code "42") (name "/ctrl6_0") (class "Default")
      (node (ref "D405") (pin "1") (pinfunction "A_1") (pintype "passive"))
      (node (ref "P-JP405") (pin "2") (pinfunction "2_2") (pintype "passive"))
      (node (ref "Q405") (pin "3") (pinfunction "C_3") (pintype "passive"))
      (node (ref "RLYI405") (pin "4") (pinfunction "4_4") (pintype "passive"))
    )
    (net (code "43") (name "/ctrl6_1") (class "Default")
      (node (ref "R-JP405") (pin "2") (pinfunction "2_2") (pintype "passive"))
      (node (ref "RLYI405") (pin "1") (pinfunction "1_1") (pintype "passive"))
    )
    (net (code "44") (name "/ctrl7_0") (class "Default")
      (node (ref "D406") (pin "1") (pinfunction "A_1") (pintype "passive"))
      (node (ref "P-JP406") (pin "2") (pinfunction "2_2") (pintype "passive"))
      (node (ref "Q406") (pin "3") (pinfunction "C_3") (pintype "passive"))
      (node (ref "RLYI406") (pin "4") (pinfunction "4_4") (pintype "passive"))
    )
    (net (code "45") (name "/ctrl7_1") (class "Default")
      (node (ref "R-JP406") (pin "2") (pinfunction "2_2") (pintype "passive"))
      (node (ref "RLYI406") (pin "1") (pinfunction "1_1") (pintype "passive"))
    )
    (net (code "46") (name "/ctrl8_0") (class "Default")
      (node (ref "D407") (pin "1") (pinfunction "A_1") (pintype "passive"))
      (node (ref "P-JP407") (pin "2") (pinfunction "2_2") (pintype "passive"))
      (node (ref "Q407") (pin "3") (pinfunction "C_3") (pintype "passive"))
      (node (ref "RLYI407") (pin "4") (pinfunction "4_4") (pintype "passive"))
    )
    (net (code "47") (name "/ctrl8_1") (class "Default")
      (node (ref "R-JP407") (pin "2") (pinfunction "2_2") (pintype "passive"))
      (node (ref "RLYI407") (pin "1") (pinfunction "1_1") (pintype "passive"))
    )
    (net (code "48") (name "/ctrl9_0") (class "Default")
      (node (ref "D408") (pin "1") (pinfunction "A_1") (pintype "passive"))
      (node (ref "P-JP408") (pin "2") (pinfunction "2_2") (pintype "passive"))
      (node (ref "Q408") (pin "3") (pinfunction "C_3") (pintype "passive"))
      (node (ref "RLYI408") (pin "4") (pinfunction "4_4") (pintype "passive"))
    )
    (net (code "49") (name "/ctrl9_1") (class "Default")
      (node (ref "R-JP408") (pin "2") (pinfunction "2_2") (pintype "passive"))
      (node (ref "RLYI408") (pin "1") (pinfunction "1_1") (pintype "passive"))
    )
    (net (code "50") (name "/ctrl10_0") (class "Default")
      (node (ref "D409") (pin "1") (pinfunction "A_1") (pintype "passive"))
      (node (ref "P-JP409") (pin "2") (pinfunction "2_2") (pintype "passive"))
      (node (ref "Q409") (pin "3") (pinfunction "C_3") (pintype "passive"))
      (node (ref "RLYI409") (pin "4") (pinfunction "4_4") (pintype "passive"))
    )
    (net (code "51") (name "/ctrl10_1") (class "Default")
      (node (ref "R-JP409") (pin "2") (pinfunction "2_2") (pintype "passive"))
      (node (ref "RLYI409") (pin "1") (pinfunction "1_1") (pintype "passive"))
    )
    (net (code "52") (name "/ctrl11_0") (class "Default")
      (node (ref "D410") (pin "1") (pinfunction "A_1") (pintype "passive"))
      (node (ref "P-JP410") (pin "2") (pinfunction "2_2") (pintype "passive"))
      (node (ref "Q410") (pin "3") (pinfunction "C_3") (pintype "passive"))
      (node (ref "RLYI410") (pin "4") (pinfunction "4_4") (pintype "passive"))
    )
    (net (code "53") (name "/ctrl11_1") (class "Default")
      (node (ref "R-JP410") (pin "2") (pinfunction "2_2") (pintype "passive"))
      (node (ref "RLYI410") (pin "1") (pinfunction "1_1") (pintype "passive"))
    )
    (net (code "54") (name "/ctrl12_0") (class "Default")
      (node (ref "D411") (pin "1") (pinfunction "A_1") (pintype "passive"))
      (node (ref "P-JP411") (pin "2") (pinfunction "2_2") (pintype "passive"))
      (node (ref "Q411") (pin "3") (pinfunction "C_3") (pintype "passive"))
      (node (ref "RLYI411") (pin "4") (pinfunction "4_4") (pintype "passive"))
    )
    (net (code "55") (name "/ctrl12_1") (class "Default")
      (node (ref "R-JP411") (pin "2") (pinfunction "2_2") (pintype "passive"))
      (node (ref "RLYI411") (pin "1") (pinfunction "1_1") (pintype "passive"))
    )
    (net (code "56") (name "/ctrl13_0") (class "Default")
      (node (ref "D412") (pin "1") (pinfunction "A_1") (pintype "passive"))
      (node (ref "P-JP412") (pin "2") (pinfunction "2_2") (pintype "passive"))
      (node (ref "Q412") (pin "3") (pinfunction "C_3") (pintype "passive"))
      (node (ref "RLYI412") (pin "4") (pinfunction "4_4") (pintype "passive"))
    )
    (net (code "57") (name "/ctrl13_1") (class "Default")
      (node (ref "R-JP412") (pin "2") (pinfunction "2_2") (pintype "passive"))
      (node (ref "RLYI412") (pin "1") (pinfunction "1_1") (pintype "passive"))
    )
    (net (code "58") (name "/ctrl14_0") (class "Default")
      (node (ref "D413") (pin "1") (pinfunction "A_1") (pintype "passive"))
      (node (ref "P-JP413") (pin "2") (pinfunction "2_2") (pintype "passive"))
      (node (ref "Q413") (pin "3") (pinfunction "C_3") (pintype "passive"))
      (node (ref "RLYI413") (pin "4") (pinfunction "4_4") (pintype "passive"))
    )
    (net (code "59") (name "/ctrl14_1") (class "Default")
      (node (ref "R-JP413") (pin "2") (pinfunction "2_2") (pintype "passive"))
      (node (ref "RLYI413") (pin "1") (pinfunction "1_1") (pintype "passive"))
    )
    (net (code "60") (name "/ctrl15_0") (class "Default")
      (node (ref "D414") (pin "1") (pinfunction "A_1") (pintype "passive"))
      (node (ref "P-JP414") (pin "2") (pinfunction "2_2") (pintype "passive"))
      (node (ref "Q414") (pin "3") (pinfunction "C_3") (pintype "passive"))
      (node (ref "RLYI414") (pin "4") (pinfunction "4_4") (pintype "passive"))
    )
    (net (code "61") (name "/ctrl15_1") (class "Default")
      (node (ref "R-JP414") (pin "2") (pinfunction "2_2") (pintype "passive"))
      (node (ref "RLYI414") (pin "1") (pinfunction "1_1") (pintype "passive"))
    )
    (net (code "62") (name "EX_GND") (class "Default")
      (node (ref "D415") (pin "1") (pinfunction "A_1") (pintype "passive"))
      (node (ref "JP401") (pin "1") (pinfunction "1_1") (pintype "passive"))
      (node (ref "Q400") (pin "2") (pinfunction "E_2") (pintype "passive"))
      (node (ref "Q401") (pin "2") (pinfunction "E_2") (pintype "passive"))
      (node (ref "Q402") (pin "2") (pinfunction "E_2") (pintype "passive"))
      (node (ref "Q403") (pin "2") (pinfunction "E_2") (pintype "passive"))
      (node (ref "Q404") (pin "2") (pinfunction "E_2") (pintype "passive"))
      (node (ref "Q405") (pin "2") (pinfunction "E_2") (pintype "passive"))
      (node (ref "Q406") (pin "2") (pinfunction "E_2") (pintype "passive"))
      (node (ref "Q407") (pin "2") (pinfunction "E_2") (pintype "passive"))
      (node (ref "Q408") (pin "2") (pinfunction "E_2") (pintype "passive"))
      (node (ref "Q409") (pin "2") (pinfunction "E_2") (pintype "passive"))
      (node (ref "Q410") (pin "2") (pinfunction "E_2") (pintype "passive"))
      (node (ref "Q411") (pin "2") (pinfunction "E_2") (pintype "passive"))
      (node (ref "Q412") (pin "2") (pinfunction "E_2") (pintype "passive"))
      (node (ref "Q413") (pin "2") (pinfunction "E_2") (pintype "passive"))
      (node (ref "Q414") (pin "2") (pinfunction "E_2") (pintype "passive"))
      (node (ref "R412") (pin "1") (pinfunction "1_1") (pintype "passive"))
      (node (ref "R413") (pin "1") (pinfunction "1_1") (pintype "passive"))
      (node (ref "R414") (pin "1") (pinfunction "1_1") (pintype "passive"))
      (node (ref "R415") (pin "1") (pinfunction "1_1") (pintype "passive"))
      (node (ref "R416") (pin "1") (pinfunction "1_1") (pintype "passive"))
      (node (ref "R417") (pin "1") (pinfunction "1_1") (pintype "passive"))
      (node (ref "R430") (pin "1") (pinfunction "1_1") (pintype "passive"))
      (node (ref "R431") (pin "1") (pinfunction "1_1") (pintype "passive"))
      (node (ref "R432") (pin "1") (pinfunction "1_1") (pintype "passive"))
      (node (ref "R433") (pin "1") (pinfunction "1_1") (pintype "passive"))
      (node (ref "R434") (pin "1") (pinfunction "1_1") (pintype "passive"))
      (node (ref "R435") (pin "1") (pinfunction "1_1") (pintype "passive"))
      (node (ref "R442") (pin "1") (pinfunction "1_1") (pintype "passive"))
      (node (ref "R443") (pin "1") (pinfunction "1_1") (pintype "passive"))
      (node (ref "R444") (pin "1") (pinfunction "1_1") (pintype "passive"))
    )
    (net (code "63") (name "EX_V+") (class "Default")
      (node (ref "D400") (pin "2") (pinfunction "K_2") (pintype "passive"))
      (node (ref "D401") (pin "2") (pinfunction "K_2") (pintype "passive"))
      (node (ref "D402") (pin "2") (pinfunction "K_2") (pintype "passive"))
      (node (ref "D403") (pin "2") (pinfunction "K_2") (pintype "passive"))
      (node (ref "D404") (pin "2") (pinfunction "K_2") (pintype "passive"))
      (node (ref "D405") (pin "2") (pinfunction "K_2") (pintype "passive"))
      (node (ref "D406") (pin "2") (pinfunction "K_2") (pintype "passive"))
      (node (ref "D407") (pin "2") (pinfunction "K_2") (pintype "passive"))
      (node (ref "D408") (pin "2") (pinfunction "K_2") (pintype "passive"))
      (node (ref "D409") (pin "2") (pinfunction "K_2") (pintype "passive"))
      (node (ref "D410") (pin "2") (pinfunction "K_2") (pintype "passive"))
      (node (ref "D411") (pin "2") (pinfunction "K_2") (pintype "passive"))
      (node (ref "D412") (pin "2") (pinfunction "K_2") (pintype "passive"))
      (node (ref "D413") (pin "2") (pinfunction "K_2") (pintype "passive"))
      (node (ref "D414") (pin "2") (pinfunction "K_2") (pintype "passive"))
      (node (ref "D415") (pin "2") (pinfunction "K_2") (pintype "passive"))
      (node (ref "JP400") (pin "1") (pinfunction "1_1") (pintype "passive"))
      (node (ref "RLYI400") (pin "3") (pinfunction "3_3") (pintype "passive"))
      (node (ref "RLYI401") (pin "3") (pinfunction "3_3") (pintype "passive"))
      (node (ref "RLYI402") (pin "3") (pinfunction "3_3") (pintype "passive"))
      (node (ref "RLYI403") (pin "3") (pinfunction "3_3") (pintype "passive"))
      (node (ref "RLYI404") (pin "3") (pinfunction "3_3") (pintype "passive"))
      (node (ref "RLYI405") (pin "3") (pinfunction "3_3") (pintype "passive"))
      (node (ref "RLYI406") (pin "3") (pinfunction "3_3") (pintype "passive"))
      (node (ref "RLYI407") (pin "3") (pinfunction "3_3") (pintype "passive"))
      (node (ref "RLYI408") (pin "3") (pinfunction "3_3") (pintype "passive"))
      (node (ref "RLYI409") (pin "3") (pinfunction "3_3") (pintype "passive"))
      (node (ref "RLYI410") (pin "3") (pinfunction "3_3") (pintype "passive"))
      (node (ref "RLYI411") (pin "3") (pinfunction "3_3") (pintype "passive"))
      (node (ref "RLYI412") (pin "3") (pinfunction "3_3") (pintype "passive"))
      (node (ref "RLYI413") (pin "3") (pinfunction "3_3") (pintype "passive"))
      (node (ref "RLYI414") (pin "3") (pinfunction "3_3") (pintype "passive"))
      (node (ref "U400") (pin "4") (pinfunction "4_4") (pintype "passive"))
      (node (ref "U401") (pin "4") (pinfunction "4_4") (pintype "passive"))
      (node (ref "U402") (pin "4") (pinfunction "4_4") (pintype "passive"))
      (node (ref "U403") (pin "4") (pinfunction "4_4") (pintype "passive"))
      (node (ref "U404") (pin "4") (pinfunction "4_4") (pintype "passive"))
      (node (ref "U405") (pin "4") (pinfunction "4_4") (pintype "passive"))
      (node (ref "U406") (pin "4") (pinfunction "4_4") (pintype "passive"))
      (node (ref "U407") (pin "4") (pinfunction "4_4") (pintype "passive"))
      (node (ref "U408") (pin "4") (pinfunction "4_4") (pintype "passive"))
      (node (ref "U409") (pin "4") (pinfunction "4_4") (pintype "passive"))
      (node (ref "U410") (pin "4") (pinfunction "4_4") (pintype "passive"))
      (node (ref "U411") (pin "4") (pinfunction "4_4") (pintype "passive"))
      (node (ref "U412") (pin "4") (pinfunction "4_4") (pintype "passive"))
      (node (ref "U413") (pin "4") (pinfunction "4_4") (pintype "passive"))
      (node (ref "U414") (pin "4") (pinfunction "4_4") (pintype "passive"))
    )
    (net (code "64") (name "GNDDIDO") (class "Default")
      (node (ref "JP401") (pin "2") (pinfunction "2_2") (pintype "passive"))
    )
    (net (code "65") (name "Net-(Q400-B)") (class "Default")
      (node (ref "Q400") (pin "1") (pinfunction "B_1") (pintype "passive"))
      (node (ref "R406") (pin "1") (pinfunction "1_1") (pintype "passive"))
      (node (ref "R412") (pin "2") (pinfunction "2_2") (pintype "passive"))
    )
    (net (code "66") (name "Net-(Q401-B)") (class "Default")
      (node (ref "Q401") (pin "1") (pinfunction "B_1") (pintype "passive"))
      (node (ref "R407") (pin "1") (pinfunction "1_1") (pintype "passive"))
      (node (ref "R413") (pin "2") (pinfunction "2_2") (pintype "passive"))
    )
    (net (code "67") (name "Net-(Q402-B)") (class "Default")
      (node (ref "Q402") (pin "1") (pinfunction "B_1") (pintype "passive"))
      (node (ref "R408") (pin "1") (pinfunction "1_1") (pintype "passive"))
      (node (ref "R414") (pin "2") (pinfunction "2_2") (pintype "passive"))
    )
    (net (code "68") (name "Net-(Q403-B)") (class "Default")
      (node (ref "Q403") (pin "1") (pinfunction "B_1") (pintype "passive"))
      (node (ref "R409") (pin "1") (pinfunction "1_1") (pintype "passive"))
      (node (ref "R415") (pin "2") (pinfunction "2_2") (pintype "passive"))
    )
    (net (code "69") (name "Net-(Q404-B)") (class "Default")
      (node (ref "Q404") (pin "1") (pinfunction "B_1") (pintype "passive"))
      (node (ref "R410") (pin "1") (pinfunction "1_1") (pintype "passive"))
      (node (ref "R416") (pin "2") (pinfunction "2_2") (pintype "passive"))
    )
    (net (code "70") (name "Net-(Q405-B)") (class "Default")
      (node (ref "Q405") (pin "1") (pinfunction "B_1") (pintype "passive"))
      (node (ref "R411") (pin "1") (pinfunction "1_1") (pintype "passive"))
      (node (ref "R417") (pin "2") (pinfunction "2_2") (pintype "passive"))
    )
    (net (code "71") (name "Net-(Q406-B)") (class "Default")
      (node (ref "Q406") (pin "1") (pinfunction "B_1") (pintype "passive"))
      (node (ref "R424") (pin "1") (pinfunction "1_1") (pintype "passive"))
      (node (ref "R430") (pin "2") (pinfunction "2_2") (pintype "passive"))
    )
    (net (code "72") (name "Net-(Q407-B)") (class "Default")
      (node (ref "Q407") (pin "1") (pinfunction "B_1") (pintype "passive"))
      (node (ref "R425") (pin "1") (pinfunction "1_1") (pintype "passive"))
      (node (ref "R431") (pin "2") (pinfunction "2_2") (pintype "passive"))
    )
    (net (code "73") (name "Net-(Q408-B)") (class "Default")
      (node (ref "Q408") (pin "1") (pinfunction "B_1") (pintype "passive"))
      (node (ref "R426") (pin "1") (pinfunction "1_1") (pintype "passive"))
      (node (ref "R432") (pin "2") (pinfunction "2_2") (pintype "passive"))
    )
    (net (code "74") (name "Net-(Q409-B)") (class "Default")
      (node (ref "Q409") (pin "1") (pinfunction "B_1") (pintype "passive"))
      (node (ref "R427") (pin "1") (pinfunction "1_1") (pintype "passive"))
      (node (ref "R433") (pin "2") (pinfunction "2_2") (pintype "passive"))
    )
    (net (code "75") (name "Net-(Q410-B)") (class "Default")
      (node (ref "Q410") (pin "1") (pinfunction "B_1") (pintype "passive"))
      (node (ref "R428") (pin "1") (pinfunction "1_1") (pintype "passive"))
      (node (ref "R434") (pin "2") (pinfunction "2_2") (pintype "passive"))
    )
    (net (code "76") (name "Net-(Q411-B)") (class "Default")
      (node (ref "Q411") (pin "1") (pinfunction "B_1") (pintype "passive"))
      (node (ref "R429") (pin "1") (pinfunction "1_1") (pintype "passive"))
      (node (ref "R435") (pin "2") (pinfunction "2_2") (pintype "passive"))
    )
    (net (code "77") (name "Net-(Q412-B)") (class "Default")
      (node (ref "Q412") (pin "1") (pinfunction "B_1") (pintype "passive"))
      (node (ref "R439") (pin "1") (pinfunction "1_1") (pintype "passive"))
      (node (ref "R442") (pin "2") (pinfunction "2_2") (pintype "passive"))
    )
    (net (code "78") (name "Net-(Q413-B)") (class "Default")
      (node (ref "Q413") (pin "1") (pinfunction "B_1") (pintype "passive"))
      (node (ref "R440") (pin "1") (pinfunction "1_1") (pintype "passive"))
      (node (ref "R443") (pin "2") (pinfunction "2_2") (pintype "passive"))
    )
    (net (code "79") (name "Net-(Q414-B)") (class "Default")
      (node (ref "Q414") (pin "1") (pinfunction "B_1") (pintype "passive"))
      (node (ref "R441") (pin "1") (pinfunction "1_1") (pintype "passive"))
      (node (ref "R444") (pin "2") (pinfunction "2_2") (pintype "passive"))
    )
    (net (code "80") (name "Net-(R400-Pad2)") (class "Default")
      (node (ref "R400") (pin "2") (pinfunction "2_2") (pintype "passive"))
      (node (ref "U400") (pin "1") (pinfunction "1_1") (pintype "passive"))
    )
    (net (code "81") (name "Net-(R401-Pad2)") (class "Default")
      (node (ref "R401") (pin "2") (pinfunction "2_2") (pintype "passive"))
      (node (ref "U401") (pin "1") (pinfunction "1_1") (pintype "passive"))
    )
    (net (code "82") (name "Net-(R402-Pad2)") (class "Default")
      (node (ref "R402") (pin "2") (pinfunction "2_2") (pintype "passive"))
      (node (ref "U402") (pin "1") (pinfunction "1_1") (pintype "passive"))
    )
    (net (code "83") (name "Net-(R403-Pad2)") (class "Default")
      (node (ref "R403") (pin "2") (pinfunction "2_2") (pintype "passive"))
      (node (ref "U403") (pin "1") (pinfunction "1_1") (pintype "passive"))
    )
    (net (code "84") (name "Net-(R404-Pad2)") (class "Default")
      (node (ref "R404") (pin "2") (pinfunction "2_2") (pintype "passive"))
      (node (ref "U404") (pin "1") (pinfunction "1_1") (pintype "passive"))
    )
    (net (code "85") (name "Net-(R405-Pad2)") (class "Default")
      (node (ref "R405") (pin "2") (pinfunction "2_2") (pintype "passive"))
      (node (ref "U405") (pin "1") (pinfunction "1_1") (pintype "passive"))
    )
    (net (code "86") (name "Net-(R406-Pad2)") (class "Default")
      (node (ref "R406") (pin "2") (pinfunction "2_2") (pintype "passive"))
      (node (ref "U400") (pin "3") (pinfunction "3_3") (pintype "passive"))
    )
    (net (code "87") (name "Net-(R407-Pad2)") (class "Default")
      (node (ref "R407") (pin "2") (pinfunction "2_2") (pintype "passive"))
      (node (ref "U401") (pin "3") (pinfunction "3_3") (pintype "passive"))
    )
    (net (code "88") (name "Net-(R408-Pad2)") (class "Default")
      (node (ref "R408") (pin "2") (pinfunction "2_2") (pintype "passive"))
      (node (ref "U402") (pin "3") (pinfunction "3_3") (pintype "passive"))
    )
    (net (code "89") (name "Net-(R409-Pad2)") (class "Default")
      (node (ref "R409") (pin "2") (pinfunction "2_2") (pintype "passive"))
      (node (ref "U403") (pin "3") (pinfunction "3_3") (pintype "passive"))
    )
    (net (code "90") (name "Net-(R410-Pad2)") (class "Default")
      (node (ref "R410") (pin "2") (pinfunction "2_2") (pintype "passive"))
      (node (ref "U404") (pin "3") (pinfunction "3_3") (pintype "passive"))
    )
    (net (code "91") (name "Net-(R411-Pad2)") (class "Default")
      (node (ref "R411") (pin "2") (pinfunction "2_2") (pintype "passive"))
      (node (ref "U405") (pin "3") (pinfunction "3_3") (pintype "passive"))
    )
    (net (code "92") (name "Net-(R418-Pad2)") (class "Default")
      (node (ref "R418") (pin "2") (pinfunction "2_2") (pintype "passive"))
      (node (ref "U406") (pin "1") (pinfunction "1_1") (pintype "passive"))
    )
    (net (code "93") (name "Net-(R419-Pad2)") (class "Default")
      (node (ref "R419") (pin "2") (pinfunction "2_2") (pintype "passive"))
      (node (ref "U407") (pin "1") (pinfunction "1_1") (pintype "passive"))
    )
    (net (code "94") (name "Net-(R420-Pad2)") (class "Default")
      (node (ref "R420") (pin "2") (pinfunction "2_2") (pintype "passive"))
      (node (ref "U408") (pin "1") (pinfunction "1_1") (pintype "passive"))
    )
    (net (code "95") (name "Net-(R421-Pad2)") (class "Default")
      (node (ref "R421") (pin "2") (pinfunction "2_2") (pintype "passive"))
      (node (ref "U409") (pin "1") (pinfunction "1_1") (pintype "passive"))
    )
    (net (code "96") (name "Net-(R422-Pad2)") (class "Default")
      (node (ref "R422") (pin "2") (pinfunction "2_2") (pintype "passive"))
      (node (ref "U410") (pin "1") (pinfunction "1_1") (pintype "passive"))
    )
    (net (code "97") (name "Net-(R423-Pad2)") (class "Default")
      (node (ref "R423") (pin "2") (pinfunction "2_2") (pintype "passive"))
      (node (ref "U411") (pin "1") (pinfunction "1_1") (pintype "passive"))
    )
    (net (code "98") (name "Net-(R424-Pad2)") (class "Default")
      (node (ref "R424") (pin "2") (pinfunction "2_2") (pintype "passive"))
      (node (ref "U406") (pin "3") (pinfunction "3_3") (pintype "passive"))
    )
    (net (code "99") (name "Net-(R425-Pad2)") (class "Default")
      (node (ref "R425") (pin "2") (pinfunction "2_2") (pintype "passive"))
      (node (ref "U407") (pin "3") (pinfunction "3_3") (pintype "passive"))
    )
    (net (code "100") (name "Net-(R426-Pad2)") (class "Default")
      (node (ref "R426") (pin "2") (pinfunction "2_2") (pintype "passive"))
      (node (ref "U408") (pin "3") (pinfunction "3_3") (pintype "passive"))
    )
    (net (code "101") (name "Net-(R427-Pad2)") (class "Default")
      (node (ref "R427") (pin "2") (pinfunction "2_2") (pintype "passive"))
      (node (ref "U409") (pin "3") (pinfunction "3_3") (pintype "passive"))
    )
    (net (code "102") (name "Net-(R428-Pad2)") (class "Default")
      (node (ref "R428") (pin "2") (pinfunction "2_2") (pintype "passive"))
      (node (ref "U410") (pin "3") (pinfunction "3_3") (pintype "passive"))
    )
    (net (code "103") (name "Net-(R429-Pad2)") (class "Default")
      (node (ref "R429") (pin "2") (pinfunction "2_2") (pintype "passive"))
      (node (ref "U411") (pin "3") (pinfunction "3_3") (pintype "passive"))
    )
    (net (code "104") (name "Net-(R436-Pad2)") (class "Default")
      (node (ref "R436") (pin "2") (pinfunction "2_2") (pintype "passive"))
      (node (ref "U412") (pin "1") (pinfunction "1_1") (pintype "passive"))
    )
    (net (code "105") (name "Net-(R437-Pad2)") (class "Default")
      (node (ref "R437") (pin "2") (pinfunction "2_2") (pintype "passive"))
      (node (ref "U413") (pin "1") (pinfunction "1_1") (pintype "passive"))
    )
    (net (code "106") (name "Net-(R438-Pad2)") (class "Default")
      (node (ref "R438") (pin "2") (pinfunction "2_2") (pintype "passive"))
      (node (ref "U414") (pin "1") (pinfunction "1_1") (pintype "passive"))
    )
    (net (code "107") (name "Net-(R439-Pad2)") (class "Default")
      (node (ref "R439") (pin "2") (pinfunction "2_2") (pintype "passive"))
      (node (ref "U412") (pin "3") (pinfunction "3_3") (pintype "passive"))
    )
    (net (code "108") (name "Net-(R440-Pad2)") (class "Default")
      (node (ref "R440") (pin "2") (pinfunction "2_2") (pintype "passive"))
      (node (ref "U413") (pin "3") (pinfunction "3_3") (pintype "passive"))
    )
    (net (code "109") (name "Net-(R441-Pad2)") (class "Default")
      (node (ref "R441") (pin "2") (pinfunction "2_2") (pintype "passive"))
      (node (ref "U414") (pin "3") (pinfunction "3_3") (pintype "passive"))
    )
    (net (code "110") (name "VCCDIDO") (class "Default")
      (node (ref "JP400") (pin "2") (pinfunction "2_2") (pintype "passive"))
    )
    (net (code "111") (name "VCCMCU_3.3") (class "Default")
      (node (ref "R400") (pin "1") (pinfunction "1_1") (pintype "passive"))
      (node (ref "R401") (pin "1") (pinfunction "1_1") (pintype "passive"))
      (node (ref "R402") (pin "1") (pinfunction "1_1") (pintype "passive"))
      (node (ref "R403") (pin "1") (pinfunction "1_1") (pintype "passive"))
      (node (ref "R404") (pin "1") (pinfunction "1_1") (pintype "passive"))
      (node (ref "R405") (pin "1") (pinfunction "1_1") (pintype "passive"))
      (node (ref "R418") (pin "1") (pinfunction "1_1") (pintype "passive"))
      (node (ref "R419") (pin "1") (pinfunction "1_1") (pintype "passive"))
      (node (ref "R420") (pin "1") (pinfunction "1_1") (pintype "passive"))
      (node (ref "R421") (pin "1") (pinfunction "1_1") (pintype "passive"))
      (node (ref "R422") (pin "1") (pinfunction "1_1") (pintype "passive"))
      (node (ref "R423") (pin "1") (pinfunction "1_1") (pintype "passive"))
      (node (ref "R436") (pin "1") (pinfunction "1_1") (pintype "passive"))
      (node (ref "R437") (pin "1") (pinfunction "1_1") (pintype "passive"))
      (node (ref "R438") (pin "1") (pinfunction "1_1") (pintype "passive"))
    )
  )
)
